# PowerSupply4ClkMezzanine.net
KiCad netlist of a schematic drawn in Altium Designer
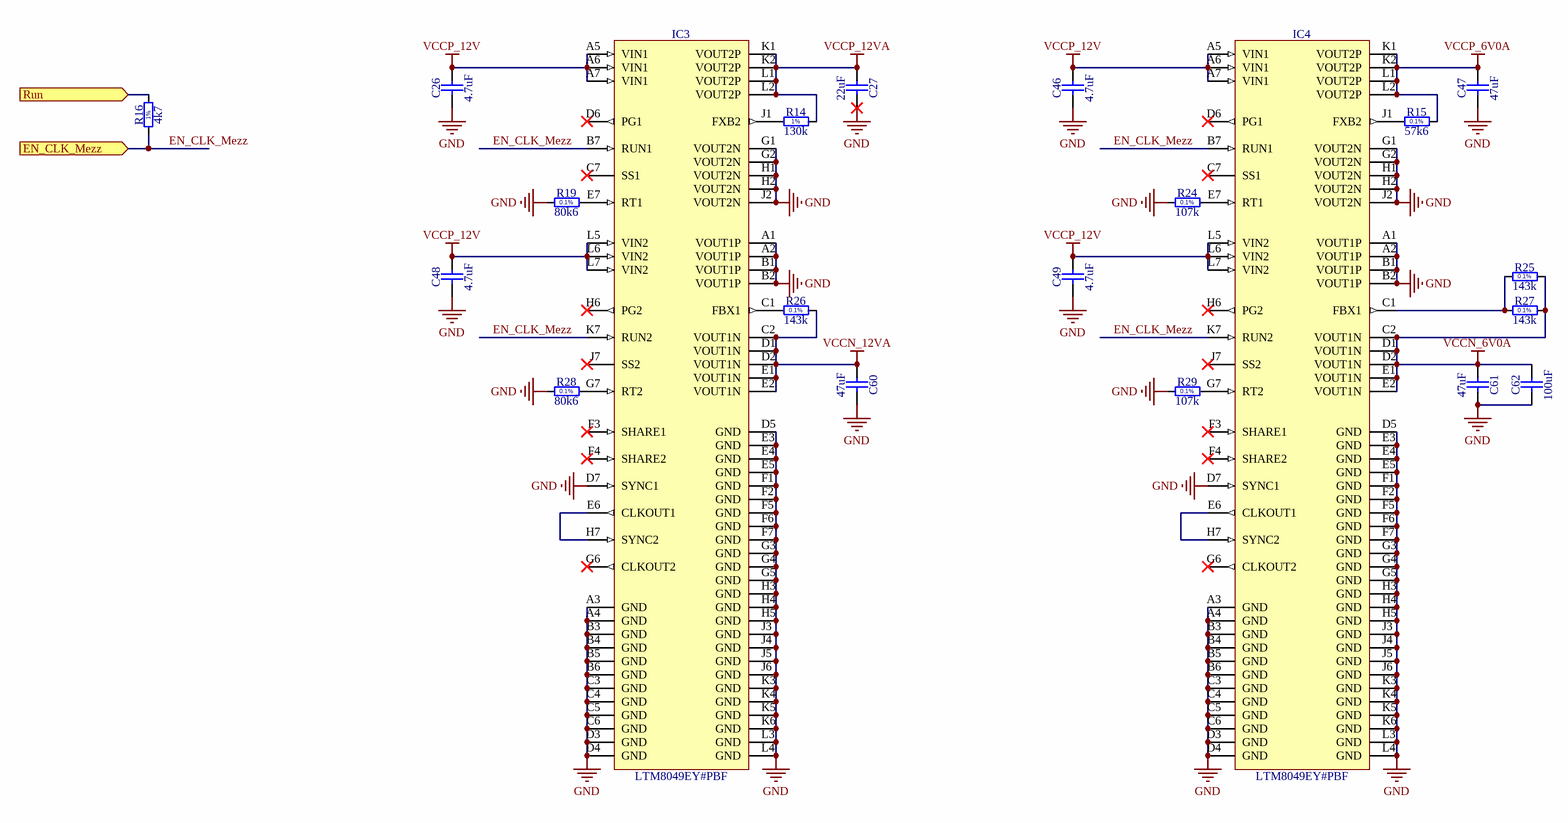
[diagram p0: PowerSupply4ClkMezzanine.SchDoc]

(export (version "E")
  (design (tool "Eeschema 10.0.6"))
  (components
    (comp (ref "C26")
      (value "4.7uF")
      (footprint "CAPC1709X95N")
      (description "Non-polarised capacitor")
      (fields
        (field (name "PART NUMBER") "CC0603_4.7UF_16V_10%_X5R")
        (field (name "VOLTAGE") "16V")
        (field (name "AUTHOR") "CERN DEM JLC")
      )
      (libsource (lib "Capacitors") (part "Capacitor - non polarized"))
    )
    (comp (ref "C27")
      (value "22uF")
      (footprint "CAPC3225X270N")
      (description "Non-polarised capacitor")
      (fields
        (field (name "PART NUMBER") "CC1210_22UF_25V_10%_X5R")
        (field (name "VOLTAGE") "25V")
        (field (name "AUTHOR") "CERN DEM JLC")
      )
      (libsource (lib "Capacitors") (part "Capacitor - non polarized"))
    )
    (comp (ref "C46")
      (value "4.7uF")
      (footprint "CAPC1709X95N")
      (description "Non-polarised capacitor")
      (fields
        (field (name "PART NUMBER") "CC0603_4.7UF_16V_10%_X5R")
        (field (name "VOLTAGE") "16V")
        (field (name "AUTHOR") "CERN DEM JLC")
      )
      (libsource (lib "Capacitors") (part "Capacitor - non polarized"))
    )
    (comp (ref "C47")
      (value "47uF")
      (footprint "CAPC3216X180N")
      (description "Non-polarised capacitor")
      (fields
        (field (name "PART NUMBER") "CC1206_47UF_25V_20%_X5R")
        (field (name "VOLTAGE") "25V")
        (field (name "AUTHOR") "CERN DEM JLC")
      )
      (libsource (lib "Capacitors") (part "Capacitor - non polarized"))
    )
    (comp (ref "C48")
      (value "4.7uF")
      (footprint "CAPC1709X95N")
      (description "Non-polarised capacitor")
      (fields
        (field (name "PART NUMBER") "CC0603_4.7UF_16V_10%_X5R")
        (field (name "VOLTAGE") "16V")
        (field (name "AUTHOR") "CERN DEM JLC")
      )
      (libsource (lib "Capacitors") (part "Capacitor - non polarized"))
    )
    (comp (ref "C49")
      (value "4.7uF")
      (footprint "CAPC1709X95N")
      (description "Non-polarised capacitor")
      (fields
        (field (name "PART NUMBER") "CC0603_4.7UF_16V_10%_X5R")
        (field (name "VOLTAGE") "16V")
        (field (name "AUTHOR") "CERN DEM JLC")
      )
      (libsource (lib "Capacitors") (part "Capacitor - non polarized"))
    )
    (comp (ref "C60")
      (value "47uF")
      (footprint "CAPC3216X180N")
      (description "Non-polarised capacitor")
      (fields
        (field (name "PART NUMBER") "CC1206_47UF_25V_20%_X5R")
        (field (name "VOLTAGE") "25V")
        (field (name "AUTHOR") "CERN DEM JLC")
      )
      (libsource (lib "Capacitors") (part "Capacitor - non polarized"))
    )
    (comp (ref "C61")
      (value "47uF")
      (footprint "CAPC3216X180N")
      (description "Non-polarised capacitor")
      (fields
        (field (name "PART NUMBER") "CC1206_47UF_25V_20%_X5R")
        (field (name "VOLTAGE") "25V")
        (field (name "AUTHOR") "CERN DEM JLC")
      )
      (libsource (lib "Capacitors") (part "Capacitor - non polarized"))
    )
    (comp (ref "C62")
      (value "100uF")
      (footprint "CAPC3216X180N")
      (description "Non-polarised capacitor")
      (fields
        (field (name "PART NUMBER") "CC1206_100UF_6.3V_20%_X5R")
        (field (name "VOLTAGE") "6.3V")
        (field (name "AUTHOR") "CERN DEM JLC")
      )
      (libsource (lib "Capacitors") (part "Capacitor - non polarized"))
    )
    (comp (ref "IC3")
      (value "LTM8049EY#PBF")
      (footprint "BGA77C127P7X11_900X1500X262")
      (description "Dual SEPIC or Inverting uModule DC/DC Converter")
      (fields (field (name "MANUFACTURER") "LINEAR TECHNOLOGY") (field (name "AUTHOR") "CERN DEM JLC"))
      (libsource (lib "ICs And Semiconductors") (part "LTM8049"))
    )
    (comp (ref "IC4")
      (value "LTM8049EY#PBF")
      (footprint "BGA77C127P7X11_900X1500X262")
      (description "Dual SEPIC or Inverting uModule DC/DC Converter")
      (fields (field (name "MANUFACTURER") "LINEAR TECHNOLOGY") (field (name "AUTHOR") "CERN DEM JLC"))
      (libsource (lib "ICs And Semiconductors") (part "LTM8049"))
    )
    (comp (ref "R14")
      (value "130k")
      (footprint "RESC1005X40N")
      (description "Resistor - 1%")
      (fields
        (field (name "PART NUMBER") "R0402_130K_1%_0.0625W_100PPM")
        (field (name "POWER") "0.0625W")
        (field (name "AUTHOR") "CERN DEM JLC")
      )
      (libsource (lib "Resistors") (part "Resistor - 1%"))
    )
    (comp (ref "R15")
      (value "57k6")
      (footprint "RESC1608X55N")
      (description "Resistor - 0.1%")
      (fields
        (field (name "PART NUMBER") "R0603_57K6_0.1%_0.063W_10PPM")
        (field (name "POWER") "0.063W")
        (field (name "AUTHOR") "CERN DEM JLC")
      )
      (libsource (lib "Resistors") (part "Resistor - 0.1%"))
    )
    (comp (ref "R16")
      (value "4k7")
      (footprint "RESC1005X40N")
      (description "Resistor - 1%")
      (fields
        (field (name "PART NUMBER") "R0402_4K7_1%_0.0625W_100PPM")
        (field (name "POWER") "0.0625W")
        (field (name "AUTHOR") "CERN DEM JLC")
      )
      (libsource (lib "Resistors") (part "Resistor - 1%"))
    )
    (comp (ref "R19")
      (value "80k6")
      (footprint "RESC1608X55N")
      (description "Resistor - 0.1%")
      (fields
        (field (name "PART NUMBER") "R0603_80K6_0.1%_0.063W_10PPM")
        (field (name "POWER") "0.063W")
        (field (name "AUTHOR") "CERN DEM JLC")
      )
      (libsource (lib "Resistors") (part "Resistor - 0.1%"))
    )
    (comp (ref "R24")
      (value "107k")
      (footprint "RESC1608X55N")
      (description "Resistor - 0.1%")
      (fields
        (field (name "PART NUMBER") "R0603_107K_0.1%_0.063W_10PPM")
        (field (name "POWER") "0.063W")
        (field (name "AUTHOR") "CERN DEM JLC")
      )
      (libsource (lib "Resistors") (part "Resistor - 0.1%"))
    )
    (comp (ref "R25")
      (value "143k")
      (footprint "RESC1608X55N")
      (description "Resistor - 0.1%")
      (fields
        (field (name "PART NUMBER") "R0603_143K_0.1%_0.063W_10PPM")
        (field (name "POWER") "0.063W")
        (field (name "AUTHOR") "CERN DEM JLC")
      )
      (libsource (lib "Resistors") (part "Resistor - 0.1%"))
    )
    (comp (ref "R26")
      (value "143k")
      (footprint "RESC1608X55N")
      (description "Resistor - 0.1%")
      (fields
        (field (name "PART NUMBER") "R0603_143K_0.1%_0.063W_10PPM")
        (field (name "POWER") "0.063W")
        (field (name "AUTHOR") "CERN DEM JLC")
      )
      (libsource (lib "Resistors") (part "Resistor - 0.1%"))
    )
    (comp (ref "R27")
      (value "143k")
      (footprint "RESC1608X55N")
      (description "Resistor - 0.1%")
      (fields
        (field (name "PART NUMBER") "R0603_143K_0.1%_0.063W_10PPM")
        (field (name "POWER") "0.063W")
        (field (name "AUTHOR") "CERN DEM JLC")
      )
      (libsource (lib "Resistors") (part "Resistor - 0.1%"))
    )
    (comp (ref "R28")
      (value "80k6")
      (footprint "RESC1608X55N")
      (description "Resistor - 0.1%")
      (fields
        (field (name "PART NUMBER") "R0603_80K6_0.1%_0.063W_10PPM")
        (field (name "POWER") "0.063W")
        (field (name "AUTHOR") "CERN DEM JLC")
      )
      (libsource (lib "Resistors") (part "Resistor - 0.1%"))
    )
    (comp (ref "R29")
      (value "107k")
      (footprint "RESC1608X55N")
      (description "Resistor - 0.1%")
      (fields
        (field (name "PART NUMBER") "R0603_107K_0.1%_0.063W_10PPM")
        (field (name "POWER") "0.063W")
        (field (name "AUTHOR") "CERN DEM JLC")
      )
      (libsource (lib "Resistors") (part "Resistor - 0.1%"))
    )
  )
  (nets
    (net (code "1") (name "/EN_CLK_Mezz") (class "Default")
      (node (ref "IC3") (pin "B7") (pinfunction "RUN1_B7") (pintype "input"))
      (node (ref "IC3") (pin "K7") (pinfunction "RUN2_K7") (pintype "input"))
      (node (ref "IC4") (pin "B7") (pinfunction "RUN1_B7") (pintype "input"))
      (node (ref "IC4") (pin "K7") (pinfunction "RUN2_K7") (pintype "input"))
      (node (ref "R16") (pin "1") (pinfunction "1_1") (pintype "passive"))
    )
    (net (code "2") (name "/Run") (class "Default")
      (node (ref "R16") (pin "2") (pinfunction "2_2") (pintype "passive"))
    )
    (net (code "3") (name "GND") (class "Default")
      (node (ref "C26") (pin "1") (pinfunction "1_1") (pintype "passive"))
      (node (ref "C27") (pin "2") (pinfunction "2_2") (pintype "passive"))
      (node (ref "C46") (pin "1") (pinfunction "1_1") (pintype "passive"))
      (node (ref "C47") (pin "1") (pinfunction "1_1") (pintype "passive"))
      (node (ref "C48") (pin "1") (pinfunction "1_1") (pintype "passive"))
      (node (ref "C49") (pin "1") (pinfunction "1_1") (pintype "passive"))
      (node (ref "C60") (pin "2") (pinfunction "2_2") (pintype "passive"))
      (node (ref "C61") (pin "2") (pinfunction "2_2") (pintype "passive"))
      (node (ref "C62") (pin "1") (pinfunction "1_1") (pintype "passive"))
      (node (ref "IC3") (pin "A1") (pinfunction "VOUT1P_A1") (pintype "power_in"))
      (node (ref "IC3") (pin "A2") (pinfunction "VOUT1P_A2") (pintype "power_in"))
      (node (ref "IC3") (pin "A3") (pinfunction "GND_A3") (pintype "open_emitter"))
      (node (ref "IC3") (pin "A4") (pinfunction "GND_A4") (pintype "open_emitter"))
      (node (ref "IC3") (pin "B1") (pinfunction "VOUT1P_B1") (pintype "power_in"))
      (node (ref "IC3") (pin "B2") (pinfunction "VOUT1P_B2") (pintype "power_in"))
      (node (ref "IC3") (pin "B3") (pinfunction "GND_B3") (pintype "open_emitter"))
      (node (ref "IC3") (pin "B4") (pinfunction "GND_B4") (pintype "open_emitter"))
      (node (ref "IC3") (pin "B5") (pinfunction "GND_B5") (pintype "open_emitter"))
      (node (ref "IC3") (pin "B6") (pinfunction "GND_B6") (pintype "open_emitter"))
      (node (ref "IC3") (pin "C3") (pinfunction "GND_C3") (pintype "open_emitter"))
      (node (ref "IC3") (pin "C4") (pinfunction "GND_C4") (pintype "open_emitter"))
      (node (ref "IC3") (pin "C5") (pinfunction "GND_C5") (pintype "open_emitter"))
      (node (ref "IC3") (pin "C6") (pinfunction "GND_C6") (pintype "open_emitter"))
      (node (ref "IC3") (pin "D3") (pinfunction "GND_D3") (pintype "open_emitter"))
      (node (ref "IC3") (pin "D4") (pinfunction "GND_D4") (pintype "open_emitter"))
      (node (ref "IC3") (pin "D5") (pinfunction "GND_D5") (pintype "open_emitter"))
      (node (ref "IC3") (pin "D7") (pinfunction "SYNC1_D7") (pintype "input"))
      (node (ref "IC3") (pin "E3") (pinfunction "GND_E3") (pintype "open_emitter"))
      (node (ref "IC3") (pin "E4") (pinfunction "GND_E4") (pintype "open_emitter"))
      (node (ref "IC3") (pin "E5") (pinfunction "GND_E5") (pintype "open_emitter"))
      (node (ref "IC3") (pin "F1") (pinfunction "GND_F1") (pintype "open_emitter"))
      (node (ref "IC3") (pin "F2") (pinfunction "GND_F2") (pintype "open_emitter"))
      (node (ref "IC3") (pin "F5") (pinfunction "GND_F5") (pintype "open_emitter"))
      (node (ref "IC3") (pin "F6") (pinfunction "GND_F6") (pintype "open_emitter"))
      (node (ref "IC3") (pin "F7") (pinfunction "GND_F7") (pintype "open_emitter"))
      (node (ref "IC3") (pin "G1") (pinfunction "VOUT2N_G1") (pintype "power_in"))
      (node (ref "IC3") (pin "G2") (pinfunction "VOUT2N_G2") (pintype "power_in"))
      (node (ref "IC3") (pin "G3") (pinfunction "GND_G3") (pintype "open_emitter"))
      (node (ref "IC3") (pin "G4") (pinfunction "GND_G4") (pintype "open_emitter"))
      (node (ref "IC3") (pin "G5") (pinfunction "GND_G5") (pintype "open_emitter"))
      (node (ref "IC3") (pin "H1") (pinfunction "VOUT2N_H1") (pintype "power_in"))
      (node (ref "IC3") (pin "H2") (pinfunction "VOUT2N_H2") (pintype "power_in"))
      (node (ref "IC3") (pin "H3") (pinfunction "GND_H3") (pintype "open_emitter"))
      (node (ref "IC3") (pin "H4") (pinfunction "GND_H4") (pintype "open_emitter"))
      (node (ref "IC3") (pin "H5") (pinfunction "GND_H5") (pintype "open_emitter"))
      (node (ref "IC3") (pin "J2") (pinfunction "VOUT2N_J2") (pintype "power_in"))
      (node (ref "IC3") (pin "J3") (pinfunction "GND_J3") (pintype "open_emitter"))
      (node (ref "IC3") (pin "J4") (pinfunction "GND_J4") (pintype "open_emitter"))
      (node (ref "IC3") (pin "J5") (pinfunction "GND_J5") (pintype "open_emitter"))
      (node (ref "IC3") (pin "J6") (pinfunction "GND_J6") (pintype "open_emitter"))
      (node (ref "IC3") (pin "K3") (pinfunction "GND_K3") (pintype "open_emitter"))
      (node (ref "IC3") (pin "K4") (pinfunction "GND_K4") (pintype "open_emitter"))
      (node (ref "IC3") (pin "K5") (pinfunction "GND_K5") (pintype "open_emitter"))
      (node (ref "IC3") (pin "K6") (pinfunction "GND_K6") (pintype "open_emitter"))
      (node (ref "IC3") (pin "L3") (pinfunction "GND_L3") (pintype "open_emitter"))
      (node (ref "IC3") (pin "L4") (pinfunction "GND_L4") (pintype "open_emitter"))
      (node (ref "IC4") (pin "A1") (pinfunction "VOUT1P_A1") (pintype "power_in"))
      (node (ref "IC4") (pin "A2") (pinfunction "VOUT1P_A2") (pintype "power_in"))
      (node (ref "IC4") (pin "A3") (pinfunction "GND_A3") (pintype "open_emitter"))
      (node (ref "IC4") (pin "A4") (pinfunction "GND_A4") (pintype "open_emitter"))
      (node (ref "IC4") (pin "B1") (pinfunction "VOUT1P_B1") (pintype "power_in"))
      (node (ref "IC4") (pin "B2") (pinfunction "VOUT1P_B2") (pintype "power_in"))
      (node (ref "IC4") (pin "B3") (pinfunction "GND_B3") (pintype "open_emitter"))
      (node (ref "IC4") (pin "B4") (pinfunction "GND_B4") (pintype "open_emitter"))
      (node (ref "IC4") (pin "B5") (pinfunction "GND_B5") (pintype "open_emitter"))
      (node (ref "IC4") (pin "B6") (pinfunction "GND_B6") (pintype "open_emitter"))
      (node (ref "IC4") (pin "C3") (pinfunction "GND_C3") (pintype "open_emitter"))
      (node (ref "IC4") (pin "C4") (pinfunction "GND_C4") (pintype "open_emitter"))
      (node (ref "IC4") (pin "C5") (pinfunction "GND_C5") (pintype "open_emitter"))
      (node (ref "IC4") (pin "C6") (pinfunction "GND_C6") (pintype "open_emitter"))
      (node (ref "IC4") (pin "D3") (pinfunction "GND_D3") (pintype "open_emitter"))
      (node (ref "IC4") (pin "D4") (pinfunction "GND_D4") (pintype "open_emitter"))
      (node (ref "IC4") (pin "D5") (pinfunction "GND_D5") (pintype "open_emitter"))
      (node (ref "IC4") (pin "D7") (pinfunction "SYNC1_D7") (pintype "input"))
      (node (ref "IC4") (pin "E3") (pinfunction "GND_E3") (pintype "open_emitter"))
      (node (ref "IC4") (pin "E4") (pinfunction "GND_E4") (pintype "open_emitter"))
      (node (ref "IC4") (pin "E5") (pinfunction "GND_E5") (pintype "open_emitter"))
      (node (ref "IC4") (pin "F1") (pinfunction "GND_F1") (pintype "open_emitter"))
      (node (ref "IC4") (pin "F2") (pinfunction "GND_F2") (pintype "open_emitter"))
      (node (ref "IC4") (pin "F5") (pinfunction "GND_F5") (pintype "open_emitter"))
      (node (ref "IC4") (pin "F6") (pinfunction "GND_F6") (pintype "open_emitter"))
      (node (ref "IC4") (pin "F7") (pinfunction "GND_F7") (pintype "open_emitter"))
      (node (ref "IC4") (pin "G1") (pinfunction "VOUT2N_G1") (pintype "power_in"))
      (node (ref "IC4") (pin "G2") (pinfunction "VOUT2N_G2") (pintype "power_in"))
      (node (ref "IC4") (pin "G3") (pinfunction "GND_G3") (pintype "open_emitter"))
      (node (ref "IC4") (pin "G4") (pinfunction "GND_G4") (pintype "open_emitter"))
      (node (ref "IC4") (pin "G5") (pinfunction "GND_G5") (pintype "open_emitter"))
      (node (ref "IC4") (pin "H1") (pinfunction "VOUT2N_H1") (pintype "power_in"))
      (node (ref "IC4") (pin "H2") (pinfunction "VOUT2N_H2") (pintype "power_in"))
      (node (ref "IC4") (pin "H3") (pinfunction "GND_H3") (pintype "open_emitter"))
      (node (ref "IC4") (pin "H4") (pinfunction "GND_H4") (pintype "open_emitter"))
      (node (ref "IC4") (pin "H5") (pinfunction "GND_H5") (pintype "open_emitter"))
      (node (ref "IC4") (pin "J2") (pinfunction "VOUT2N_J2") (pintype "power_in"))
      (node (ref "IC4") (pin "J3") (pinfunction "GND_J3") (pintype "open_emitter"))
      (node (ref "IC4") (pin "J4") (pinfunction "GND_J4") (pintype "open_emitter"))
      (node (ref "IC4") (pin "J5") (pinfunction "GND_J5") (pintype "open_emitter"))
      (node (ref "IC4") (pin "J6") (pinfunction "GND_J6") (pintype "open_emitter"))
      (node (ref "IC4") (pin "K3") (pinfunction "GND_K3") (pintype "open_emitter"))
      (node (ref "IC4") (pin "K4") (pinfunction "GND_K4") (pintype "open_emitter"))
      (node (ref "IC4") (pin "K5") (pinfunction "GND_K5") (pintype "open_emitter"))
      (node (ref "IC4") (pin "K6") (pinfunction "GND_K6") (pintype "open_emitter"))
      (node (ref "IC4") (pin "L3") (pinfunction "GND_L3") (pintype "open_emitter"))
      (node (ref "IC4") (pin "L4") (pinfunction "GND_L4") (pintype "open_emitter"))
      (node (ref "R19") (pin "1") (pinfunction "1_1") (pintype "passive"))
      (node (ref "R24") (pin "1") (pinfunction "1_1") (pintype "passive"))
      (node (ref "R28") (pin "1") (pinfunction "1_1") (pintype "passive"))
      (node (ref "R29") (pin "1") (pinfunction "1_1") (pintype "passive"))
    )
    (net (code "4") (name "Net-(IC3-CLKOUT1)") (class "Default")
      (node (ref "IC3") (pin "E6") (pinfunction "CLKOUT1_E6") (pintype "output"))
      (node (ref "IC3") (pin "H7") (pinfunction "SYNC2_H7") (pintype "input"))
    )
    (net (code "5") (name "Net-(IC3-FBX1)") (class "Default")
      (node (ref "IC3") (pin "C1") (pinfunction "FBX1_C1") (pintype "output"))
      (node (ref "R26") (pin "1") (pinfunction "1_1") (pintype "passive"))
    )
    (net (code "6") (name "Net-(IC3-FXB2)") (class "Default")
      (node (ref "IC3") (pin "J1") (pinfunction "FXB2_J1") (pintype "output"))
      (node (ref "R14") (pin "1") (pinfunction "1_1") (pintype "passive"))
    )
    (net (code "7") (name "Net-(IC3-RT1)") (class "Default")
      (node (ref "IC3") (pin "E7") (pinfunction "RT1_E7") (pintype "input"))
      (node (ref "R19") (pin "2") (pinfunction "2_2") (pintype "passive"))
    )
    (net (code "8") (name "Net-(IC3-RT2)") (class "Default")
      (node (ref "IC3") (pin "G7") (pinfunction "RT2_G7") (pintype "input"))
      (node (ref "R28") (pin "2") (pinfunction "2_2") (pintype "passive"))
    )
    (net (code "9") (name "Net-(IC4-CLKOUT1)") (class "Default")
      (node (ref "IC4") (pin "E6") (pinfunction "CLKOUT1_E6") (pintype "output"))
      (node (ref "IC4") (pin "H7") (pinfunction "SYNC2_H7") (pintype "input"))
    )
    (net (code "10") (name "Net-(IC4-FBX1)") (class "Default")
      (node (ref "IC4") (pin "C1") (pinfunction "FBX1_C1") (pintype "output"))
      (node (ref "R25") (pin "1") (pinfunction "1_1") (pintype "passive"))
      (node (ref "R27") (pin "1") (pinfunction "1_1") (pintype "passive"))
    )
    (net (code "11") (name "Net-(IC4-FXB2)") (class "Default")
      (node (ref "IC4") (pin "J1") (pinfunction "FXB2_J1") (pintype "output"))
      (node (ref "R15") (pin "1") (pinfunction "1_1") (pintype "passive"))
    )
    (net (code "12") (name "Net-(IC4-RT1)") (class "Default")
      (node (ref "IC4") (pin "E7") (pinfunction "RT1_E7") (pintype "input"))
      (node (ref "R24") (pin "2") (pinfunction "2_2") (pintype "passive"))
    )
    (net (code "13") (name "Net-(IC4-RT2)") (class "Default")
      (node (ref "IC4") (pin "G7") (pinfunction "RT2_G7") (pintype "input"))
      (node (ref "R29") (pin "2") (pinfunction "2_2") (pintype "passive"))
    )
    (net (code "14") (name "VCCN_6V0A") (class "Default")
      (node (ref "C61") (pin "1") (pinfunction "1_1") (pintype "passive"))
      (node (ref "C62") (pin "2") (pinfunction "2_2") (pintype "passive"))
      (node (ref "IC4") (pin "C2") (pinfunction "VOUT1N_C2") (pintype "power_in"))
      (node (ref "IC4") (pin "D1") (pinfunction "VOUT1N_D1") (pintype "power_in"))
      (node (ref "IC4") (pin "D2") (pinfunction "VOUT1N_D2") (pintype "power_in"))
      (node (ref "IC4") (pin "E1") (pinfunction "VOUT1N_E1") (pintype "power_in"))
      (node (ref "IC4") (pin "E2") (pinfunction "VOUT1N_E2") (pintype "power_in"))
      (node (ref "R25") (pin "2") (pinfunction "2_2") (pintype "passive"))
      (node (ref "R27") (pin "2") (pinfunction "2_2") (pintype "passive"))
    )
    (net (code "15") (name "VCCN_12VA") (class "Default")
      (node (ref "C60") (pin "1") (pinfunction "1_1") (pintype "passive"))
      (node (ref "IC3") (pin "C2") (pinfunction "VOUT1N_C2") (pintype "power_in"))
      (node (ref "IC3") (pin "D1") (pinfunction "VOUT1N_D1") (pintype "power_in"))
      (node (ref "IC3") (pin "D2") (pinfunction "VOUT1N_D2") (pintype "power_in"))
      (node (ref "IC3") (pin "E1") (pinfunction "VOUT1N_E1") (pintype "power_in"))
      (node (ref "IC3") (pin "E2") (pinfunction "VOUT1N_E2") (pintype "power_in"))
      (node (ref "R26") (pin "2") (pinfunction "2_2") (pintype "passive"))
    )
    (net (code "16") (name "VCCP_6V0A") (class "Default")
      (node (ref "C47") (pin "2") (pinfunction "2_2") (pintype "passive"))
      (node (ref "IC4") (pin "K1") (pinfunction "VOUT2P_K1") (pintype "power_in"))
      (node (ref "IC4") (pin "K2") (pinfunction "VOUT2P_K2") (pintype "power_in"))
      (node (ref "IC4") (pin "L1") (pinfunction "VOUT2P_L1") (pintype "power_in"))
      (node (ref "IC4") (pin "L2") (pinfunction "VOUT2P_L2") (pintype "power_in"))
      (node (ref "R15") (pin "2") (pinfunction "2_2") (pintype "passive"))
    )
    (net (code "17") (name "VCCP_12V") (class "Default")
      (node (ref "C26") (pin "2") (pinfunction "2_2") (pintype "passive"))
      (node (ref "C46") (pin "2") (pinfunction "2_2") (pintype "passive"))
      (node (ref "C48") (pin "2") (pinfunction "2_2") (pintype "passive"))
      (node (ref "C49") (pin "2") (pinfunction "2_2") (pintype "passive"))
      (node (ref "IC3") (pin "A5") (pinfunction "VIN1_A5") (pintype "input"))
      (node (ref "IC3") (pin "A6") (pinfunction "VIN1_A6") (pintype "input"))
      (node (ref "IC3") (pin "A7") (pinfunction "VIN1_A7") (pintype "input"))
      (node (ref "IC3") (pin "L5") (pinfunction "VIN2_L5") (pintype "input"))
      (node (ref "IC3") (pin "L6") (pinfunction "VIN2_L6") (pintype "input"))
      (node (ref "IC3") (pin "L7") (pinfunction "VIN2_L7") (pintype "input"))
      (node (ref "IC4") (pin "A5") (pinfunction "VIN1_A5") (pintype "input"))
      (node (ref "IC4") (pin "A6") (pinfunction "VIN1_A6") (pintype "input"))
      (node (ref "IC4") (pin "A7") (pinfunction "VIN1_A7") (pintype "input"))
      (node (ref "IC4") (pin "L5") (pinfunction "VIN2_L5") (pintype "input"))
      (node (ref "IC4") (pin "L6") (pinfunction "VIN2_L6") (pintype "input"))
      (node (ref "IC4") (pin "L7") (pinfunction "VIN2_L7") (pintype "input"))
    )
    (net (code "18") (name "VCCP_12VA") (class "Default")
      (node (ref "C27") (pin "1") (pinfunction "1_1") (pintype "passive"))
      (node (ref "IC3") (pin "K1") (pinfunction "VOUT2P_K1") (pintype "power_in"))
      (node (ref "IC3") (pin "K2") (pinfunction "VOUT2P_K2") (pintype "power_in"))
      (node (ref "IC3") (pin "L1") (pinfunction "VOUT2P_L1") (pintype "power_in"))
      (node (ref "IC3") (pin "L2") (pinfunction "VOUT2P_L2") (pintype "power_in"))
      (node (ref "R14") (pin "2") (pinfunction "2_2") (pintype "passive"))
    )
    (net (code "19") (name "unconnected-(IC3-CLKOUT2-PadG6)") (class "Default")
      (node (ref "IC3") (pin "G6") (pinfunction "CLKOUT2_G6") (pintype "output+no_connect"))
    )
    (net (code "20") (name "unconnected-(IC3-PG1-PadD6)") (class "Default")
      (node (ref "IC3") (pin "D6") (pinfunction "PG1_D6") (pintype "output+no_connect"))
    )
    (net (code "21") (name "unconnected-(IC3-PG2-PadH6)") (class "Default")
      (node (ref "IC3") (pin "H6") (pinfunction "PG2_H6") (pintype "output+no_connect"))
    )
    (net (code "22") (name "unconnected-(IC3-SHARE1-PadF3)") (class "Default")
      (node (ref "IC3") (pin "F3") (pinfunction "SHARE1_F3") (pintype "input+no_connect"))
    )
    (net (code "23") (name "unconnected-(IC3-SHARE2-PadF4)") (class "Default")
      (node (ref "IC3") (pin "F4") (pinfunction "SHARE2_F4") (pintype "input+no_connect"))
    )
    (net (code "24") (name "unconnected-(IC3-SS1-PadC7)") (class "Default")
      (node (ref "IC3") (pin "C7") (pinfunction "SS1_C7") (pintype "passive+no_connect"))
    )
    (net (code "25") (name "unconnected-(IC3-SS2-PadJ7)") (class "Default")
      (node (ref "IC3") (pin "J7") (pinfunction "SS2_J7") (pintype "passive+no_connect"))
    )
    (net (code "26") (name "unconnected-(IC4-CLKOUT2-PadG6)") (class "Default")
      (node (ref "IC4") (pin "G6") (pinfunction "CLKOUT2_G6") (pintype "output+no_connect"))
    )
    (net (code "27") (name "unconnected-(IC4-PG1-PadD6)") (class "Default")
      (node (ref "IC4") (pin "D6") (pinfunction "PG1_D6") (pintype "output+no_connect"))
    )
    (net (code "28") (name "unconnected-(IC4-PG2-PadH6)") (class "Default")
      (node (ref "IC4") (pin "H6") (pinfunction "PG2_H6") (pintype "output+no_connect"))
    )
    (net (code "29") (name "unconnected-(IC4-SHARE1-PadF3)") (class "Default")
      (node (ref "IC4") (pin "F3") (pinfunction "SHARE1_F3") (pintype "input+no_connect"))
    )
    (net (code "30") (name "unconnected-(IC4-SHARE2-PadF4)") (class "Default")
      (node (ref "IC4") (pin "F4") (pinfunction "SHARE2_F4") (pintype "input+no_connect"))
    )
    (net (code "31") (name "unconnected-(IC4-SS1-PadC7)") (class "Default")
      (node (ref "IC4") (pin "C7") (pinfunction "SS1_C7") (pintype "passive+no_connect"))
    )
    (net (code "32") (name "unconnected-(IC4-SS2-PadJ7)") (class "Default")
      (node (ref "IC4") (pin "J7") (pinfunction "SS2_J7") (pintype "passive+no_connect"))
    )
  )
)
